# TPI_Carte_Alimentation.net
KiCad netlist of a schematic drawn in Altium Designer
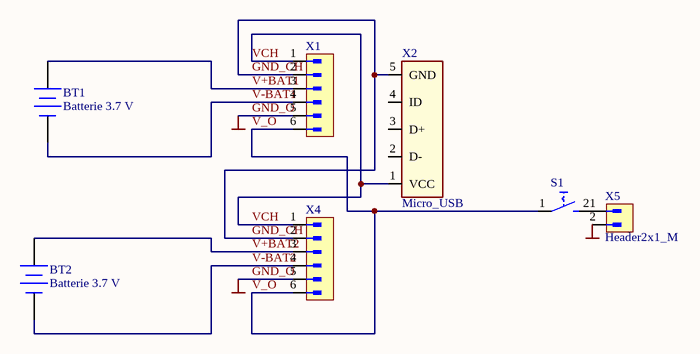
[diagram p0: TPI_Carte_Alimentation.SchDoc]

(export (version "E")
  (design (tool "Eeschema 10.0.6"))
  (components
    (comp (ref "BT1")
      (value "Batterie 3.7 V")
      (footprint "18650Holder_V1")
      (description "Multicell Battery")
      (fields (field (name "PUBLISHER") "Altium Limited"))
      (libsource (lib "Miscellaneous Devices") (part "Battery"))
    )
    (comp (ref "BT2")
      (value "Batterie 3.7 V")
      (footprint "CPNV:18650Holder_V1")
      (description "Multicell Battery")
      (fields (field (name "PUBLISHER") "Altium Limited"))
      (libsource (lib "Miscellaneous Devices") (part "Battery"))
    )
    (comp (ref "S1")
      (value "?")
      (footprint "MOLEX_0022284020")
      (description "Switch Normaly Open")
      (libsource (lib "altium-import") (part "root_0_Switch_NO_"))
    )
    (comp (ref "X1")
      (value "Header6x1_M")
      (footprint "HDR6X1_M")
      (fields
        (field (name "MANUFACTURER PART NUMBER") "61300611121")
        (field (name "MANUFACTURER") "Wurth Electronics")
        (field (name "SOURCE") "MEION_Connectors.SchLib")
      )
      (libsource (lib "CPNV Centre professionnel du Nord vaudois") (part "Header6x1_M"))
    )
    (comp (ref "X2")
      (value "Micro_USB")
      (footprint "MICRO_USB")
      (libsource (lib "altium-import") (part "root_0_Micro_USB_"))
    )
    (comp (ref "X4")
      (value "Header6x1_M")
      (footprint "HDR6X1_M")
      (fields
        (field (name "MANUFACTURER PART NUMBER") "61300611121")
        (field (name "MANUFACTURER") "Wurth Electronics")
        (field (name "SOURCE") "MEION_Connectors.SchLib")
      )
      (libsource (lib "CPNV Centre professionnel du Nord vaudois") (part "Header6x1_M"))
    )
    (comp (ref "X5")
      (value "Header2x1_M")
      (footprint "HDR2X1_M")
      (description "WR-PHD 2.54 mm THT Pin Header")
      (fields
        (field (name "MANUFACTURER PART NUMBER") "61300211121")
        (field (name "MANUFACTURER") "Wurth Electronics")
        (field (name "SOURCE") "MEION_Connectors.SchLib")
      )
      (libsource (lib "CPNV Centre professionnel du Nord vaudois") (part "Header2x1_M"))
    )
  )
  (nets
    (net (code "1") (name "/GND_CH") (class "Default")
      (node (ref "X1") (pin "2") (pinfunction "2_2") (pintype "passive"))
      (node (ref "X2") (pin "5") (pinfunction "GND_5") (pintype "power_in"))
      (node (ref "X4") (pin "2") (pinfunction "2_2") (pintype "passive"))
    )
    (net (code "2") (name "/V+BAT1") (class "Default")
      (node (ref "BT1") (pin "1") (pinfunction "+_1") (pintype "passive"))
      (node (ref "X1") (pin "3") (pinfunction "3_3") (pintype "passive"))
    )
    (net (code "3") (name "/V+BAT2") (class "Default")
      (node (ref "BT2") (pin "1") (pinfunction "+_1") (pintype "passive"))
      (node (ref "X4") (pin "3") (pinfunction "3_3") (pintype "passive"))
    )
    (net (code "4") (name "/V-BAT1") (class "Default")
      (node (ref "BT1") (pin "2") (pinfunction "-_2") (pintype "passive"))
      (node (ref "X1") (pin "4") (pinfunction "4_4") (pintype "passive"))
    )
    (net (code "5") (name "/V-BAT2") (class "Default")
      (node (ref "BT2") (pin "2") (pinfunction "-_2") (pintype "passive"))
      (node (ref "X4") (pin "4") (pinfunction "4_4") (pintype "passive"))
    )
    (net (code "6") (name "/VCH") (class "Default")
      (node (ref "X1") (pin "1") (pinfunction "1_1") (pintype "passive"))
      (node (ref "X2") (pin "1") (pinfunction "VCC_1") (pintype "passive"))
      (node (ref "X4") (pin "1") (pinfunction "1_1") (pintype "passive"))
    )
    (net (code "7") (name "/V_O") (class "Default")
      (node (ref "S1") (pin "1") (pinfunction "1_1") (pintype "passive"))
      (node (ref "X1") (pin "6") (pinfunction "6_6") (pintype "passive"))
      (node (ref "X4") (pin "6") (pinfunction "6_6") (pintype "passive"))
    )
    (net (code "8") (name "GND") (class "Default")
      (node (ref "X1") (pin "5") (pinfunction "5_5") (pintype "passive"))
      (node (ref "X4") (pin "5") (pinfunction "5_5") (pintype "passive"))
      (node (ref "X5") (pin "2") (pinfunction "2_2") (pintype "passive"))
    )
    (net (code "9") (name "Net-(S1-Pad2)") (class "Default")
      (node (ref "S1") (pin "2") (pinfunction "2_2") (pintype "passive"))
      (node (ref "X5") (pin "1") (pinfunction "1_1") (pintype "passive"))
    )
    (net (code "10") (name "unconnected-(X2-D+-Pad3)") (class "Default")
      (node (ref "X2") (pin "3") (pinfunction "D+_3") (pintype "passive"))
    )
    (net (code "11") (name "unconnected-(X2-D--Pad2)") (class "Default")
      (node (ref "X2") (pin "2") (pinfunction "D-_2") (pintype "passive"))
    )
    (net (code "12") (name "unconnected-(X2-ID-Pad4)") (class "Default")
      (node (ref "X2") (pin "4") (pinfunction "ID_4") (pintype "passive"))
    )
  )
)
